# E4PRJ4PSU.net
KiCad netlist of a schematic drawn in EAGLE
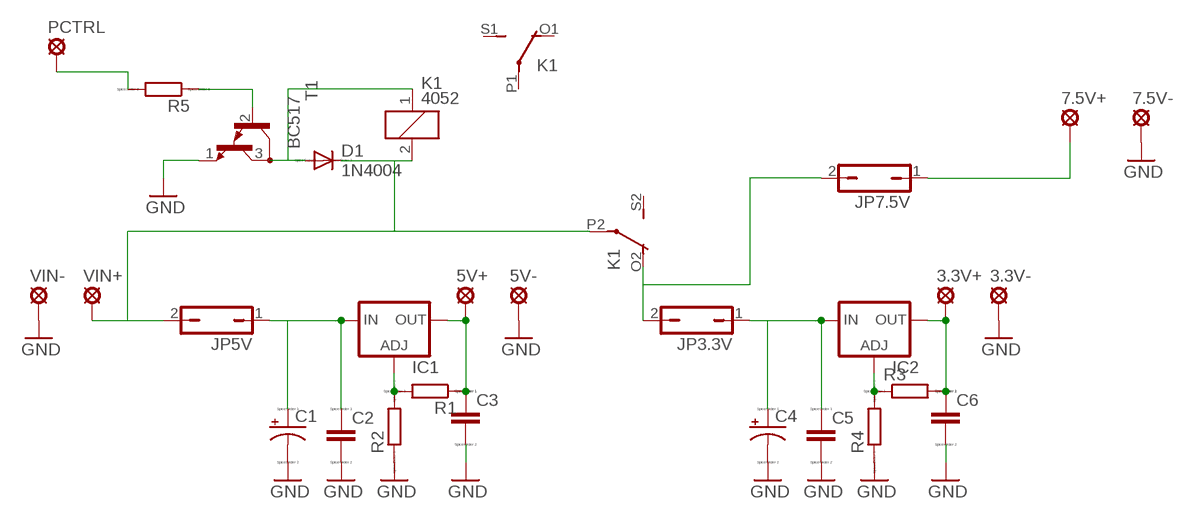
[diagram p0: schematic, sheet 1]

(export (version "E")
  (design (tool "Eeschema 10.0.6"))
  (components
    (comp (ref "3.3V+")
      (value "SE14")
      (footprint "eagle-import:SE14")
      (libsource (lib "eagle-import") (part "SE14"))
    )
    (comp (ref "3.3V-")
      (value "SE14")
      (footprint "eagle-import:SE14")
      (libsource (lib "eagle-import") (part "SE14"))
    )
    (comp (ref "5V+")
      (value "SE14")
      (footprint "eagle-import:SE14")
      (libsource (lib "eagle-import") (part "SE14"))
    )
    (comp (ref "5V-")
      (value "SE14")
      (footprint "eagle-import:SE14")
      (libsource (lib "eagle-import") (part "SE14"))
    )
    (comp (ref "7.5V+")
      (value "SE14")
      (footprint "eagle-import:SE14")
      (libsource (lib "eagle-import") (part "SE14"))
    )
    (comp (ref "7.5V-")
      (value "SE14")
      (footprint "eagle-import:SE14")
      (libsource (lib "eagle-import") (part "SE14"))
    )
    (comp (ref "C1")
      (value "CPOL-USE5-10.5")
      (footprint "eagle-import:E5-10,5")
      (libsource (lib "eagle-import") (part "CPOL-USE5-10.5"))
    )
    (comp (ref "C2")
      (value "C-EU050-025X075")
      (footprint "eagle-import:C050-025X075")
      (libsource (lib "eagle-import") (part "C-EU050-025X075"))
    )
    (comp (ref "C3")
      (value "C-EU050-025X075")
      (footprint "eagle-import:C050-025X075")
      (libsource (lib "eagle-import") (part "C-EU050-025X075"))
    )
    (comp (ref "C4")
      (value "CPOL-USE5-10.5")
      (footprint "eagle-import:E5-10,5")
      (libsource (lib "eagle-import") (part "CPOL-USE5-10.5"))
    )
    (comp (ref "C5")
      (value "C-EU050-025X075")
      (footprint "eagle-import:C050-025X075")
      (libsource (lib "eagle-import") (part "C-EU050-025X075"))
    )
    (comp (ref "C6")
      (value "C-EU050-025X075")
      (footprint "eagle-import:C050-025X075")
      (libsource (lib "eagle-import") (part "C-EU050-025X075"))
    )
    (comp (ref "D1")
      (value "1N4004")
      (footprint "eagle-import:DO41-10")
      (libsource (lib "eagle-import") (part "1N4004"))
    )
    (comp (ref "IC1")
      (value "LM317TS")
      (footprint "eagle-import:317TS")
      (libsource (lib "eagle-import") (part "LM317TS"))
    )
    (comp (ref "IC2")
      (value "LM317TS")
      (footprint "eagle-import:317TS")
      (libsource (lib "eagle-import") (part "LM317TS"))
    )
    (comp (ref "JP3.3V")
      (value "JP1Q")
      (footprint "eagle-import:JP1")
      (libsource (lib "eagle-import") (part "JP1Q"))
    )
    (comp (ref "JP5V")
      (value "JP1Q")
      (footprint "eagle-import:JP1")
      (libsource (lib "eagle-import") (part "JP1Q"))
    )
    (comp (ref "JP7.5V")
      (value "JP1Q")
      (footprint "eagle-import:JP1")
      (libsource (lib "eagle-import") (part "JP1Q"))
    )
    (comp (ref "K1")
      (value "4052")
      (footprint "eagle-import:F4052")
      (libsource (lib "eagle-import") (part "4052"))
    )
    (comp (ref "PCTRL")
      (value "SE14")
      (footprint "eagle-import:SE14")
      (libsource (lib "eagle-import") (part "SE14"))
    )
    (comp (ref "R1")
      (value "R-EU_0207_10")
      (footprint "eagle-import:0207_10")
      (libsource (lib "eagle-import") (part "R-EU_0207_10"))
    )
    (comp (ref "R2")
      (value "R-EU_0207_10")
      (footprint "eagle-import:0207_10")
      (libsource (lib "eagle-import") (part "R-EU_0207_10"))
    )
    (comp (ref "R3")
      (value "R-EU_0207_10")
      (footprint "eagle-import:0207_10")
      (libsource (lib "eagle-import") (part "R-EU_0207_10"))
    )
    (comp (ref "R4")
      (value "R-EU_0207_10")
      (footprint "eagle-import:0207_10")
      (libsource (lib "eagle-import") (part "R-EU_0207_10"))
    )
    (comp (ref "R5")
      (value "R-EU_0207_10")
      (footprint "eagle-import:0207_10")
      (libsource (lib "eagle-import") (part "R-EU_0207_10"))
    )
    (comp (ref "T1")
      (value "BC517")
      (footprint "eagle-import:TO92")
      (libsource (lib "eagle-import") (part "BC517"))
    )
    (comp (ref "VIN+")
      (value "SE14")
      (footprint "eagle-import:SE14")
      (libsource (lib "eagle-import") (part "SE14"))
    )
    (comp (ref "VIN-")
      (value "SE14")
      (footprint "eagle-import:SE14")
      (libsource (lib "eagle-import") (part "SE14"))
    )
  )
  (nets
    (net (code "1") (name "GND") (class "Default")
      (node (ref "3.3V-") (pin "MP") (pinfunction "MP_MP") (pintype "passive"))
      (node (ref "5V-") (pin "MP") (pinfunction "MP_MP") (pintype "passive"))
      (node (ref "7.5V-") (pin "MP") (pinfunction "MP_MP") (pintype "passive"))
      (node (ref "C1") (pin "-") (pinfunction "-_-") (pintype "passive"))
      (node (ref "C2") (pin "2") (pinfunction "2_2") (pintype "passive"))
      (node (ref "C3") (pin "2") (pinfunction "2_2") (pintype "passive"))
      (node (ref "C4") (pin "-") (pinfunction "-_-") (pintype "passive"))
      (node (ref "C5") (pin "2") (pinfunction "2_2") (pintype "passive"))
      (node (ref "C6") (pin "2") (pinfunction "2_2") (pintype "passive"))
      (node (ref "R2") (pin "1") (pinfunction "1_1") (pintype "passive"))
      (node (ref "R4") (pin "1") (pinfunction "1_1") (pintype "passive"))
      (node (ref "T1") (pin "1") (pinfunction "E_1") (pintype "passive"))
      (node (ref "VIN-") (pin "MP") (pinfunction "MP_MP") (pintype "passive"))
    )
    (net (code "2") (name "Net-(7.5V+-PadMP)") (class "Default")
      (node (ref "7.5V+") (pin "MP") (pinfunction "MP_MP") (pintype "passive"))
      (node (ref "JP7.5V") (pin "1") (pinfunction "1_1") (pintype "passive"))
    )
    (net (code "3") (name "Net-(IC1-ADJ)") (class "Default")
      (node (ref "IC1") (pin "1") (pinfunction "ADJ_1") (pintype "input"))
      (node (ref "R1") (pin "2") (pinfunction "2_2") (pintype "passive"))
      (node (ref "R2") (pin "2") (pinfunction "2_2") (pintype "passive"))
    )
    (net (code "4") (name "Net-(IC1-IN)") (class "Default")
      (node (ref "C1") (pin "+") (pinfunction "+_+") (pintype "passive"))
      (node (ref "C2") (pin "1") (pinfunction "1_1") (pintype "passive"))
      (node (ref "IC1") (pin "3") (pinfunction "IN_3") (pintype "input"))
      (node (ref "JP5V") (pin "1") (pinfunction "1_1") (pintype "passive"))
    )
    (net (code "5") (name "Net-(IC1-OUT)") (class "Default")
      (node (ref "5V+") (pin "MP") (pinfunction "MP_MP") (pintype "passive"))
      (node (ref "C3") (pin "1") (pinfunction "1_1") (pintype "passive"))
      (node (ref "IC1") (pin "2") (pinfunction "OUT_2") (pintype "passive"))
      (node (ref "R1") (pin "1") (pinfunction "1_1") (pintype "passive"))
    )
    (net (code "6") (name "Net-(IC2-ADJ)") (class "Default")
      (node (ref "IC2") (pin "1") (pinfunction "ADJ_1") (pintype "input"))
      (node (ref "R3") (pin "1") (pinfunction "1_1") (pintype "passive"))
      (node (ref "R4") (pin "2") (pinfunction "2_2") (pintype "passive"))
    )
    (net (code "7") (name "Net-(IC2-IN)") (class "Default")
      (node (ref "C4") (pin "+") (pinfunction "+_+") (pintype "passive"))
      (node (ref "C5") (pin "1") (pinfunction "1_1") (pintype "passive"))
      (node (ref "IC2") (pin "3") (pinfunction "IN_3") (pintype "input"))
      (node (ref "JP3.3V") (pin "1") (pinfunction "1_1") (pintype "passive"))
    )
    (net (code "8") (name "Net-(IC2-OUT)") (class "Default")
      (node (ref "3.3V+") (pin "MP") (pinfunction "MP_MP") (pintype "passive"))
      (node (ref "C6") (pin "1") (pinfunction "1_1") (pintype "passive"))
      (node (ref "IC2") (pin "2") (pinfunction "OUT_2") (pintype "passive"))
      (node (ref "R3") (pin "2") (pinfunction "2_2") (pintype "passive"))
    )
    (net (code "9") (name "Net-(K1C-O)") (class "Default")
      (node (ref "JP3.3V") (pin "2") (pinfunction "2_2") (pintype "passive"))
      (node (ref "JP7.5V") (pin "2") (pinfunction "2_2") (pintype "passive"))
      (node (ref "K1") (pin "O2") (pinfunction "O_O2") (pintype "passive"))
    )
    (net (code "10") (name "Net-(K1C-P)") (class "Default")
      (node (ref "D1") (pin "C") (pinfunction "C_C") (pintype "passive"))
      (node (ref "JP5V") (pin "2") (pinfunction "2_2") (pintype "passive"))
      (node (ref "K1") (pin "2") (pinfunction "2_2") (pintype "passive"))
      (node (ref "K1") (pin "P2") (pinfunction "P_P2") (pintype "passive"))
      (node (ref "VIN+") (pin "MP") (pinfunction "MP_MP") (pintype "passive"))
    )
    (net (code "11") (name "Net-(PCTRL-PadMP)") (class "Default")
      (node (ref "PCTRL") (pin "MP") (pinfunction "MP_MP") (pintype "passive"))
      (node (ref "R5") (pin "2") (pinfunction "2_2") (pintype "passive"))
    )
    (net (code "12") (name "Net-(T1-B)") (class "Default")
      (node (ref "R5") (pin "1") (pinfunction "1_1") (pintype "passive"))
      (node (ref "T1") (pin "2") (pinfunction "B_2") (pintype "passive"))
    )
    (net (code "13") (name "Net-(T1-C)") (class "Default")
      (node (ref "D1") (pin "A") (pinfunction "A_A") (pintype "passive"))
      (node (ref "K1") (pin "1") (pinfunction "1_1") (pintype "passive"))
      (node (ref "T1") (pin "3") (pinfunction "C_3") (pintype "passive"))
    )
    (net (code "14") (name "unconnected-(K1B-O-PadO1)") (class "Default")
      (node (ref "K1") (pin "O1") (pinfunction "O_O1") (pintype "passive"))
    )
    (net (code "15") (name "unconnected-(K1B-P-PadP1)") (class "Default")
      (node (ref "K1") (pin "P1") (pinfunction "P_P1") (pintype "passive"))
    )
    (net (code "16") (name "unconnected-(K1B-S-PadS1)") (class "Default")
      (node (ref "K1") (pin "S1") (pinfunction "S_S1") (pintype "passive"))
    )
    (net (code "17") (name "unconnected-(K1C-S-PadS2)") (class "Default")
      (node (ref "K1") (pin "S2") (pinfunction "S_S2") (pintype "passive"))
    )
  )
)
